# thruster_plate.net
KiCad netlist of a schematic drawn in EAGLE
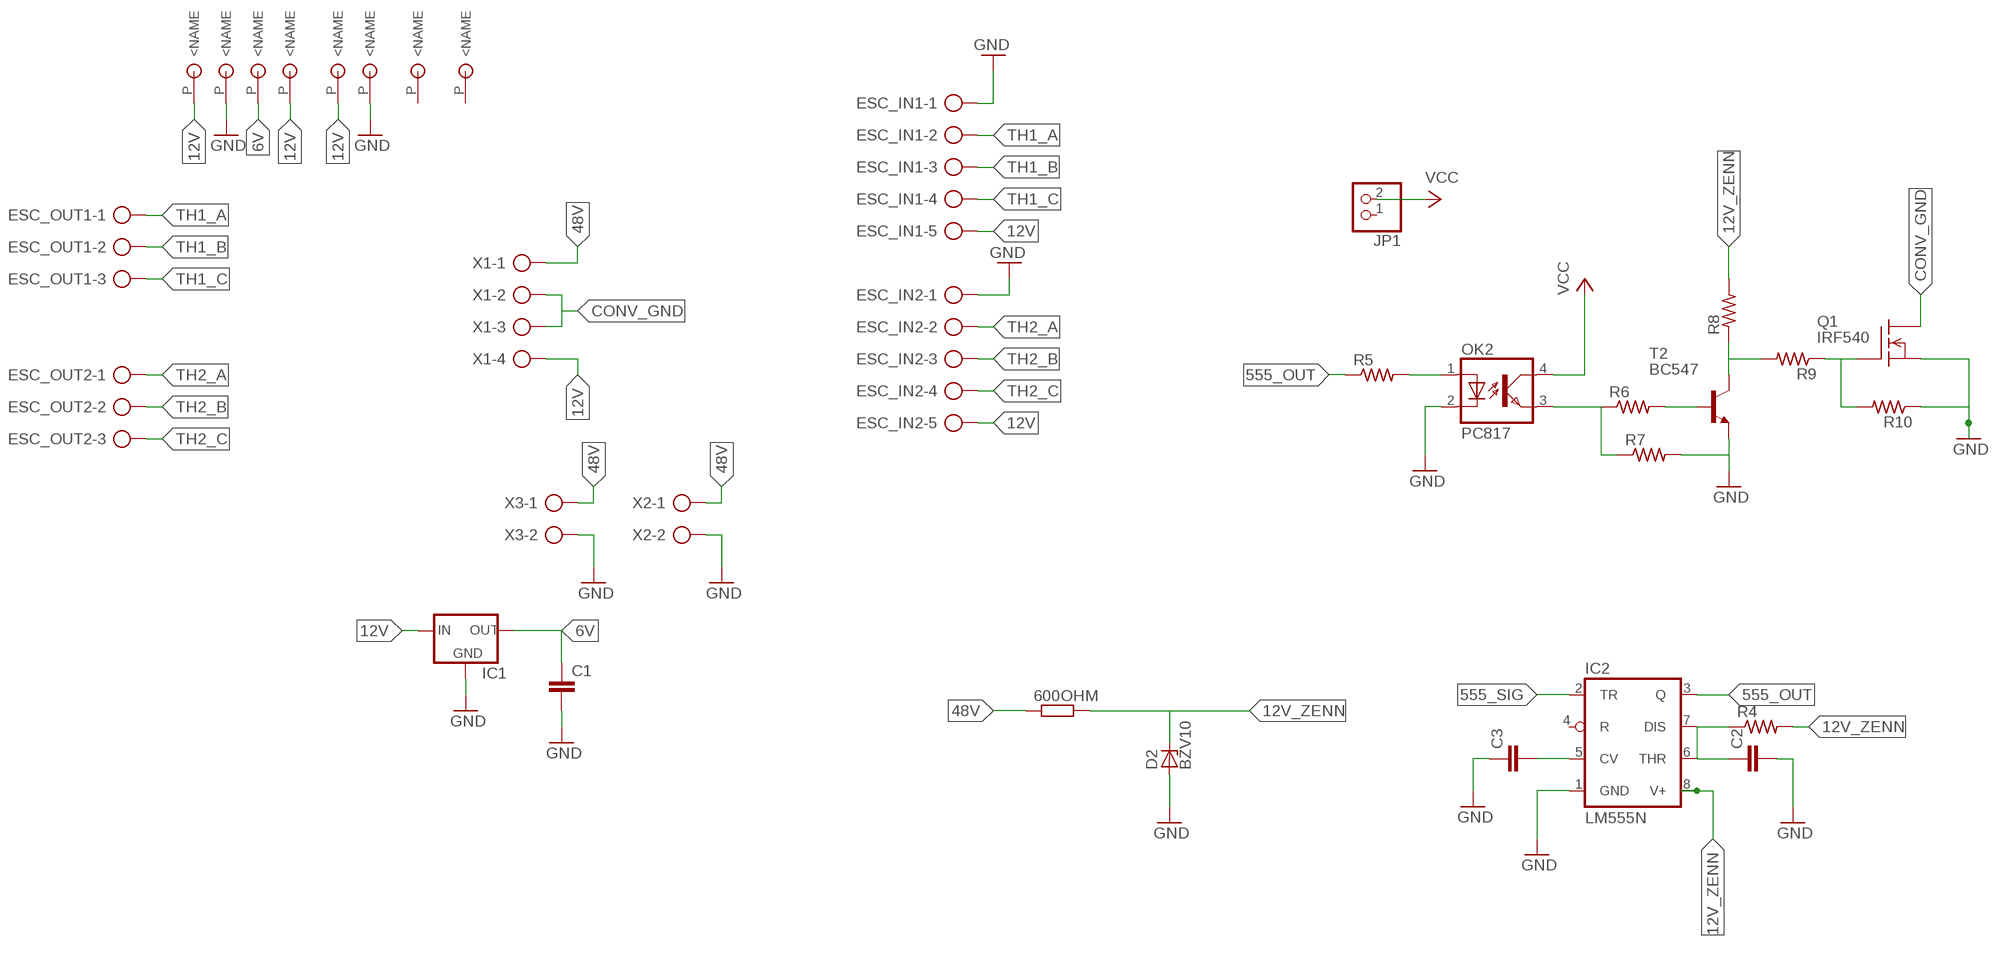
[diagram p0: schematic, sheet 1]

(export (version "E")
  (design (tool "Eeschema 10.0.6"))
  (components
    (comp (ref "12")
      (value "CU-SPACER")
      (footprint "eagle-import:CU-SPACER")
      (libsource (lib "eagle-import") (part "CU-SPACER"))
    )
    (comp (ref "12-1")
      (value "CU-SPACER")
      (footprint "eagle-import:CU-SPACER")
      (libsource (lib "eagle-import") (part "CU-SPACER"))
    )
    (comp (ref "12-2")
      (value "CU-SPACER")
      (footprint "eagle-import:CU-SPACER")
      (libsource (lib "eagle-import") (part "CU-SPACER"))
    )
    (comp (ref "12-3")
      (value "CU-SPACER")
      (footprint "eagle-import:CU-SPACER")
      (libsource (lib "eagle-import") (part "CU-SPACER"))
    )
    (comp (ref "12-4")
      (value "CU-SPACER")
      (footprint "eagle-import:CU-SPACER")
      (libsource (lib "eagle-import") (part "CU-SPACER"))
    )
    (comp (ref "12-6")
      (value "CU-SPACER")
      (footprint "eagle-import:CU-SPACER")
      (libsource (lib "eagle-import") (part "CU-SPACER"))
    )
    (comp (ref "600OHM")
      (value "R-EU_V235/17")
      (footprint "eagle-import:V235_17")
      (libsource (lib "eagle-import") (part "R-EU_V235/17"))
    )
    (comp (ref "C1")
      (value "C-EU050-024X044")
      (footprint "eagle-import:C050-024X044")
      (libsource (lib "eagle-import") (part "C-EU050-024X044"))
    )
    (comp (ref "C2")
      (value "C-EU050-035X075")
      (footprint "eagle-import:C050-035X075")
      (libsource (lib "eagle-import") (part "C-EU050-035X075"))
    )
    (comp (ref "C3")
      (value "C-EU050-024X044")
      (footprint "eagle-import:C050-024X044")
      (libsource (lib "eagle-import") (part "C-EU050-024X044"))
    )
    (comp (ref "D2")
      (value "BZV10")
      (footprint "eagle-import:DO34Z7")
      (libsource (lib "eagle-import") (part "BZV10"))
    )
    (comp (ref "ESC_IN1")
      (value "AK500/5")
      (footprint "eagle-import:AK500_5")
      (libsource (lib "eagle-import") (part "AK500/5"))
    )
    (comp (ref "ESC_IN2")
      (value "AK500/5")
      (footprint "eagle-import:AK500_5")
      (libsource (lib "eagle-import") (part "AK500/5"))
    )
    (comp (ref "ESC_OUT1")
      (value "AK500/3")
      (footprint "eagle-import:AK500_3")
      (libsource (lib "eagle-import") (part "AK500/3"))
    )
    (comp (ref "ESC_OUT2")
      (value "AK500/3")
      (footprint "eagle-import:AK500_3")
      (libsource (lib "eagle-import") (part "AK500/3"))
    )
    (comp (ref "IC1")
      (value "78XXL")
      (footprint "eagle-import:78XXL")
      (libsource (lib "eagle-import") (part "78XXL"))
    )
    (comp (ref "IC2")
      (value "LM555N")
      (footprint "eagle-import:DIL08")
      (libsource (lib "eagle-import") (part "555NLM"))
    )
    (comp (ref "JP1")
      (value "PINHD-1X2")
      (footprint "eagle-import:1X02")
      (libsource (lib "eagle-import") (part "PINHD-1X2"))
    )
    (comp (ref "OK2")
      (value "PC817")
      (footprint "eagle-import:DIL04")
      (fields (field (name "MPN") "PC817X4J000F"))
      (libsource (lib "eagle-import") (part "PC817"))
    )
    (comp (ref "Q1")
      (value "IRF540")
      (footprint "eagle-import:TO220")
      (libsource (lib "eagle-import") (part "IRF540"))
    )
    (comp (ref "R4")
      (value "R-US_0204/7")
      (footprint "eagle-import:0204_7")
      (libsource (lib "eagle-import") (part "R-US_0204/7"))
    )
    (comp (ref "R5")
      (value "R-US_0204/7")
      (footprint "eagle-import:0204_7")
      (libsource (lib "eagle-import") (part "R-US_0204/7"))
    )
    (comp (ref "R6")
      (value "R-US_0204/7")
      (footprint "eagle-import:0204_7")
      (libsource (lib "eagle-import") (part "R-US_0204/7"))
    )
    (comp (ref "R7")
      (value "R-US_0204/7")
      (footprint "eagle-import:0204_7")
      (libsource (lib "eagle-import") (part "R-US_0204/7"))
    )
    (comp (ref "R8")
      (value "R-US_0204/7")
      (footprint "eagle-import:0204_7")
      (libsource (lib "eagle-import") (part "R-US_0204/7"))
    )
    (comp (ref "R9")
      (value "R-US_0204/7")
      (footprint "eagle-import:0204_7")
      (libsource (lib "eagle-import") (part "R-US_0204/7"))
    )
    (comp (ref "R10")
      (value "R-US_0204/7")
      (footprint "eagle-import:0204_7")
      (libsource (lib "eagle-import") (part "R-US_0204/7"))
    )
    (comp (ref "T2")
      (value "BC547")
      (footprint "eagle-import:TO92")
      (libsource (lib "eagle-import") (part "BC547"))
    )
    (comp (ref "U$2")
      (value "CU-SPACER")
      (footprint "eagle-import:CU-SPACER")
      (libsource (lib "eagle-import") (part "CU-SPACER"))
    )
    (comp (ref "U$3")
      (value "CU-SPACER")
      (footprint "eagle-import:CU-SPACER")
      (libsource (lib "eagle-import") (part "CU-SPACER"))
    )
    (comp (ref "X1")
      (value "AK500/4")
      (footprint "eagle-import:AK500_4")
      (libsource (lib "eagle-import") (part "AK500/4"))
    )
    (comp (ref "X2")
      (value "AK500/2")
      (footprint "eagle-import:AK500_2")
      (libsource (lib "eagle-import") (part "AK500/2"))
    )
    (comp (ref "X3")
      (value "AK500/2")
      (footprint "eagle-import:AK500_2")
      (libsource (lib "eagle-import") (part "AK500/2"))
    )
  )
  (nets
    (net (code "1") (name "6V") (class "Default")
      (node (ref "C1") (pin "1") (pinfunction "1_1") (pintype "passive"))
      (node (ref "IC1") (pin "OUT") (pinfunction "OUT_OUT") (pintype "passive"))
      (node (ref "U$3") (pin "P") (pinfunction "<NAME_P") (pintype "bidirectional"))
    )
    (net (code "2") (name "12V") (class "Default")
      (node (ref "12") (pin "P") (pinfunction "<NAME_P") (pintype "bidirectional"))
      (node (ref "12-1") (pin "P") (pinfunction "<NAME_P") (pintype "bidirectional"))
      (node (ref "12-2") (pin "P") (pinfunction "<NAME_P") (pintype "bidirectional"))
      (node (ref "ESC_IN1") (pin "5") (pinfunction "KL_5") (pintype "passive"))
      (node (ref "ESC_IN2") (pin "5") (pinfunction "KL_5") (pintype "passive"))
      (node (ref "IC1") (pin "IN") (pinfunction "IN_IN") (pintype "input"))
      (node (ref "X1") (pin "4") (pinfunction "KL_4") (pintype "passive"))
    )
    (net (code "3") (name "12V_ZENN") (class "Default")
      (node (ref "600OHM") (pin "2") (pinfunction "2_2") (pintype "passive"))
      (node (ref "D2") (pin "C") (pinfunction "C_C") (pintype "passive"))
      (node (ref "IC2") (pin "8") (pinfunction "V+_8") (pintype "power_in"))
      (node (ref "R4") (pin "2") (pinfunction "2_2") (pintype "passive"))
      (node (ref "R8") (pin "2") (pinfunction "2_2") (pintype "passive"))
    )
    (net (code "4") (name "48V") (class "Default")
      (node (ref "600OHM") (pin "1") (pinfunction "1_1") (pintype "passive"))
      (node (ref "X1") (pin "1") (pinfunction "KL_1") (pintype "passive"))
      (node (ref "X2") (pin "1") (pinfunction "KL_1") (pintype "passive"))
      (node (ref "X3") (pin "1") (pinfunction "KL_1") (pintype "passive"))
    )
    (net (code "5") (name "555_OUT") (class "Default")
      (node (ref "IC2") (pin "3") (pinfunction "Q_3") (pintype "output"))
      (node (ref "R5") (pin "1") (pinfunction "1_1") (pintype "passive"))
    )
    (net (code "6") (name "555_SIG") (class "Default")
      (node (ref "IC2") (pin "2") (pinfunction "TR_2") (pintype "input"))
    )
    (net (code "7") (name "CONV_GND") (class "Default")
      (node (ref "Q1") (pin "2") (pinfunction "D_2") (pintype "passive"))
      (node (ref "X1") (pin "2") (pinfunction "KL_2") (pintype "passive"))
      (node (ref "X1") (pin "3") (pinfunction "KL_3") (pintype "passive"))
    )
    (net (code "8") (name "GND") (class "Default")
      (node (ref "12-3") (pin "P") (pinfunction "<NAME_P") (pintype "bidirectional"))
      (node (ref "C1") (pin "2") (pinfunction "2_2") (pintype "passive"))
      (node (ref "C2") (pin "2") (pinfunction "2_2") (pintype "passive"))
      (node (ref "C3") (pin "1") (pinfunction "1_1") (pintype "passive"))
      (node (ref "D2") (pin "A") (pinfunction "A_A") (pintype "passive"))
      (node (ref "ESC_IN1") (pin "1") (pinfunction "KL_1") (pintype "passive"))
      (node (ref "ESC_IN2") (pin "1") (pinfunction "KL_1") (pintype "passive"))
      (node (ref "IC1") (pin "GND") (pinfunction "GND_GND") (pintype "input"))
      (node (ref "IC2") (pin "1") (pinfunction "GND_1") (pintype "power_in"))
      (node (ref "OK2") (pin "2") (pinfunction "C_2") (pintype "passive"))
      (node (ref "Q1") (pin "3") (pinfunction "S_3") (pintype "passive"))
      (node (ref "R10") (pin "1") (pinfunction "1_1") (pintype "passive"))
      (node (ref "R7") (pin "2") (pinfunction "2_2") (pintype "passive"))
      (node (ref "T2") (pin "1") (pinfunction "E_1") (pintype "passive"))
      (node (ref "U$2") (pin "P") (pinfunction "<NAME_P") (pintype "bidirectional"))
      (node (ref "X2") (pin "2") (pinfunction "KL_2") (pintype "passive"))
      (node (ref "X3") (pin "2") (pinfunction "KL_2") (pintype "passive"))
    )
    (net (code "9") (name "Net-(IC2-CV)") (class "Default")
      (node (ref "C3") (pin "2") (pinfunction "2_2") (pintype "passive"))
      (node (ref "IC2") (pin "5") (pinfunction "CV_5") (pintype "input"))
    )
    (net (code "10") (name "Net-(IC2-DIS)") (class "Default")
      (node (ref "C2") (pin "1") (pinfunction "1_1") (pintype "passive"))
      (node (ref "IC2") (pin "6") (pinfunction "THR_6") (pintype "input"))
      (node (ref "IC2") (pin "7") (pinfunction "DIS_7") (pintype "input"))
      (node (ref "R4") (pin "1") (pinfunction "1_1") (pintype "passive"))
    )
    (net (code "11") (name "Net-(OK2-A)") (class "Default")
      (node (ref "OK2") (pin "1") (pinfunction "A_1") (pintype "passive"))
      (node (ref "R5") (pin "2") (pinfunction "2_2") (pintype "passive"))
    )
    (net (code "12") (name "Net-(OK2-EMIT)") (class "Default")
      (node (ref "OK2") (pin "3") (pinfunction "EMIT_3") (pintype "passive"))
      (node (ref "R6") (pin "1") (pinfunction "1_1") (pintype "passive"))
      (node (ref "R7") (pin "1") (pinfunction "1_1") (pintype "passive"))
    )
    (net (code "13") (name "Net-(Q1-G)") (class "Default")
      (node (ref "Q1") (pin "1") (pinfunction "G_1") (pintype "passive"))
      (node (ref "R10") (pin "2") (pinfunction "2_2") (pintype "passive"))
      (node (ref "R9") (pin "1") (pinfunction "1_1") (pintype "passive"))
    )
    (net (code "14") (name "Net-(T2-B)") (class "Default")
      (node (ref "R6") (pin "2") (pinfunction "2_2") (pintype "passive"))
      (node (ref "T2") (pin "2") (pinfunction "B_2") (pintype "passive"))
    )
    (net (code "15") (name "Net-(T2-C)") (class "Default")
      (node (ref "R8") (pin "1") (pinfunction "1_1") (pintype "passive"))
      (node (ref "R9") (pin "2") (pinfunction "2_2") (pintype "passive"))
      (node (ref "T2") (pin "3") (pinfunction "C_3") (pintype "passive"))
    )
    (net (code "16") (name "TH1_A") (class "Default")
      (node (ref "ESC_IN1") (pin "2") (pinfunction "KL_2") (pintype "passive"))
      (node (ref "ESC_OUT1") (pin "1") (pinfunction "KL_1") (pintype "passive"))
    )
    (net (code "17") (name "TH1_B") (class "Default")
      (node (ref "ESC_IN1") (pin "3") (pinfunction "KL_3") (pintype "passive"))
      (node (ref "ESC_OUT1") (pin "2") (pinfunction "KL_2") (pintype "passive"))
    )
    (net (code "18") (name "TH1_C") (class "Default")
      (node (ref "ESC_IN1") (pin "4") (pinfunction "KL_4") (pintype "passive"))
      (node (ref "ESC_OUT1") (pin "3") (pinfunction "KL_3") (pintype "passive"))
    )
    (net (code "19") (name "TH2_A") (class "Default")
      (node (ref "ESC_IN2") (pin "2") (pinfunction "KL_2") (pintype "passive"))
      (node (ref "ESC_OUT2") (pin "1") (pinfunction "KL_1") (pintype "passive"))
    )
    (net (code "20") (name "TH2_B") (class "Default")
      (node (ref "ESC_IN2") (pin "3") (pinfunction "KL_3") (pintype "passive"))
      (node (ref "ESC_OUT2") (pin "2") (pinfunction "KL_2") (pintype "passive"))
    )
    (net (code "21") (name "TH2_C") (class "Default")
      (node (ref "ESC_IN2") (pin "4") (pinfunction "KL_4") (pintype "passive"))
      (node (ref "ESC_OUT2") (pin "3") (pinfunction "KL_3") (pintype "passive"))
    )
    (net (code "22") (name "VCC") (class "Default")
      (node (ref "JP1") (pin "2") (pinfunction "2_2") (pintype "passive"))
      (node (ref "OK2") (pin "4") (pinfunction "COL_4") (pintype "passive"))
    )
    (net (code "23") (name "unconnected-(12-4-<NAME-PadP)") (class "Default")
      (node (ref "12-4") (pin "P") (pinfunction "<NAME_P") (pintype "bidirectional"))
    )
    (net (code "24") (name "unconnected-(12-6-<NAME-PadP)") (class "Default")
      (node (ref "12-6") (pin "P") (pinfunction "<NAME_P") (pintype "bidirectional"))
    )
    (net (code "25") (name "unconnected-(IC2-R-Pad4)") (class "Default")
      (node (ref "IC2") (pin "4") (pinfunction "R_4") (pintype "input"))
    )
    (net (code "26") (name "unconnected-(JP1-Pad1)") (class "Default")
      (node (ref "JP1") (pin "1") (pinfunction "1_1") (pintype "passive"))
    )
  )
)
